# NerfPWM_V1_1.net
KiCad netlist of a schematic drawn in EAGLE
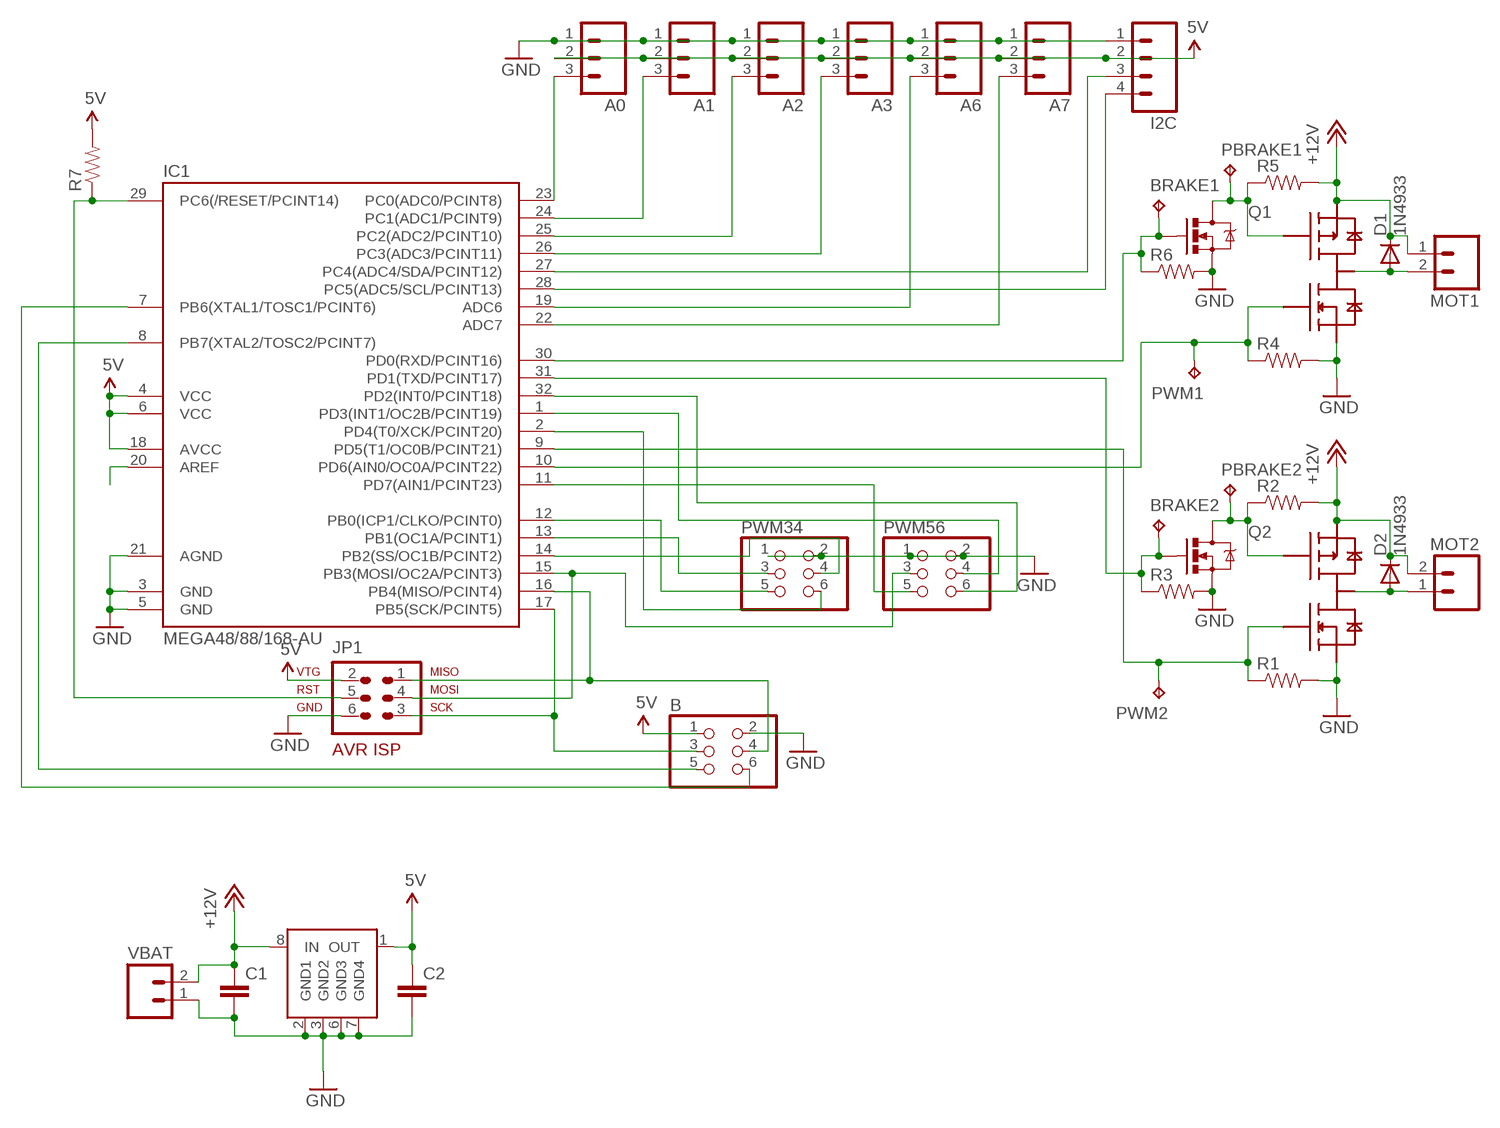
[diagram p0: schematic, sheet 1]

(export (version "E")
  (design (tool "Eeschema 10.0.6"))
  (components
    (comp (ref "A0")
      (value "M03PTH")
      (footprint "eagle-import:1X03")
      (libsource (lib "eagle-import") (part "M03PTH"))
    )
    (comp (ref "A1")
      (value "M03PTH")
      (footprint "eagle-import:1X03")
      (libsource (lib "eagle-import") (part "M03PTH"))
    )
    (comp (ref "A2")
      (value "M03PTH")
      (footprint "eagle-import:1X03")
      (libsource (lib "eagle-import") (part "M03PTH"))
    )
    (comp (ref "A3")
      (value "M03PTH")
      (footprint "eagle-import:1X03")
      (libsource (lib "eagle-import") (part "M03PTH"))
    )
    (comp (ref "A6")
      (value "M03PTH")
      (footprint "eagle-import:1X03")
      (libsource (lib "eagle-import") (part "M03PTH"))
    )
    (comp (ref "A7")
      (value "M03PTH")
      (footprint "eagle-import:1X03")
      (libsource (lib "eagle-import") (part "M03PTH"))
    )
    (comp (ref "B")
      (value "PINHD-2X3")
      (footprint "eagle-import:2X03")
      (libsource (lib "eagle-import") (part "PINHD-2X3"))
    )
    (comp (ref "BRAKE1")
      (value "TPTP10R")
      (footprint "eagle-import:TP10R")
      (libsource (lib "eagle-import") (part "TPTP10R"))
    )
    (comp (ref "BRAKE2")
      (value "TPTP10R")
      (footprint "eagle-import:TP10R")
      (libsource (lib "eagle-import") (part "TPTP10R"))
    )
    (comp (ref "C1")
      (value "CAP1206")
      (footprint "eagle-import:1206")
      (libsource (lib "eagle-import") (part "CAP1206"))
    )
    (comp (ref "C2")
      (value "CAP1206")
      (footprint "eagle-import:1206")
      (libsource (lib "eagle-import") (part "CAP1206"))
    )
    (comp (ref "D1")
      (value "1N4933")
      (footprint "eagle-import:DO41-10")
      (libsource (lib "eagle-import") (part "1N4933"))
    )
    (comp (ref "D2")
      (value "1N4933")
      (footprint "eagle-import:DO41-10")
      (libsource (lib "eagle-import") (part "1N4933"))
    )
    (comp (ref "I2C")
      (value "M04PTH")
      (footprint "eagle-import:1X04")
      (libsource (lib "eagle-import") (part "M04PTH"))
    )
    (comp (ref "IC1")
      (value "MEGA48/88/168-AU")
      (footprint "eagle-import:TQFP32-08")
      (libsource (lib "eagle-import") (part "MEGA48/88/168-AU"))
    )
    (comp (ref "JP1")
      (value "AVR-ISP-6")
      (footprint "eagle-import:AVR-ISP-6")
      (libsource (lib "eagle-import") (part "AVR-ISP-6"))
    )
    (comp (ref "MOT1")
      (value "M023.5MM_LOCK")
      (footprint "eagle-import:SCREWTERMINAL-3.5MM-2_LOCK")
      (libsource (lib "eagle-import") (part "M023.5MM_LOCK"))
    )
    (comp (ref "MOT2")
      (value "M023.5MM_LOCK")
      (footprint "eagle-import:SCREWTERMINAL-3.5MM-2_LOCK")
      (libsource (lib "eagle-import") (part "M023.5MM_LOCK"))
    )
    (comp (ref "PBRAKE1")
      (value "TPTP10R")
      (footprint "eagle-import:TP10R")
      (libsource (lib "eagle-import") (part "TPTP10R"))
    )
    (comp (ref "PBRAKE2")
      (value "TPTP10R")
      (footprint "eagle-import:TP10R")
      (libsource (lib "eagle-import") (part "TPTP10R"))
    )
    (comp (ref "PWM1")
      (value "TPTP10R")
      (footprint "eagle-import:TP10R")
      (libsource (lib "eagle-import") (part "TPTP10R"))
    )
    (comp (ref "PWM2")
      (value "TPTP10R")
      (footprint "eagle-import:TP10R")
      (libsource (lib "eagle-import") (part "TPTP10R"))
    )
    (comp (ref "PWM34")
      (value "PINHD-2X3")
      (footprint "eagle-import:2X03")
      (libsource (lib "eagle-import") (part "PINHD-2X3"))
    )
    (comp (ref "PWM56")
      (value "PINHD-2X3")
      (footprint "eagle-import:2X03")
      (libsource (lib "eagle-import") (part "PINHD-2X3"))
    )
    (comp (ref "Q1")
      (value "MOSFET-NCHANNELSMD")
      (footprint "eagle-import:SOT23-3")
      (libsource (lib "eagle-import") (part "MOSFET-NCHANNELSMD"))
    )
    (comp (ref "Q2")
      (value "MOSFET-NCHANNELSMD")
      (footprint "eagle-import:SOT23-3")
      (libsource (lib "eagle-import") (part "MOSFET-NCHANNELSMD"))
    )
    (comp (ref "R1")
      (value "RESISTOR")
      (footprint "eagle-import:0805")
      (libsource (lib "eagle-import") (part "RESISTOR"))
    )
    (comp (ref "R2")
      (value "RESISTOR")
      (footprint "eagle-import:0805")
      (libsource (lib "eagle-import") (part "RESISTOR"))
    )
    (comp (ref "R3")
      (value "RESISTOR")
      (footprint "eagle-import:0805")
      (libsource (lib "eagle-import") (part "RESISTOR"))
    )
    (comp (ref "R4")
      (value "RESISTOR")
      (footprint "eagle-import:0805")
      (libsource (lib "eagle-import") (part "RESISTOR"))
    )
    (comp (ref "R5")
      (value "RESISTOR")
      (footprint "eagle-import:0805")
      (libsource (lib "eagle-import") (part "RESISTOR"))
    )
    (comp (ref "R6")
      (value "RESISTOR")
      (footprint "eagle-import:0805")
      (libsource (lib "eagle-import") (part "RESISTOR"))
    )
    (comp (ref "R7")
      (value "RESISTOR")
      (footprint "eagle-import:0805")
      (libsource (lib "eagle-import") (part "RESISTOR"))
    )
    (comp (ref "U$3")
      (value "MC78L00AD")
      (footprint "eagle-import:SOIC8")
      (libsource (lib "eagle-import") (part "MC78L00AD"))
    )
    (comp (ref "U$4")
      (value "SI4501BDY")
      (footprint "eagle-import:SOIC8")
      (libsource (lib "eagle-import") (part "SI4501BDY"))
    )
    (comp (ref "U$5")
      (value "SI4501BDY")
      (footprint "eagle-import:SOIC8")
      (libsource (lib "eagle-import") (part "SI4501BDY"))
    )
    (comp (ref "VBAT")
      (value "M023.5MM_LOCK")
      (footprint "eagle-import:SCREWTERMINAL-3.5MM-2_LOCK")
      (libsource (lib "eagle-import") (part "M023.5MM_LOCK"))
    )
  )
  (nets
    (net (code "1") (name "+12V") (class "Default")
      (node (ref "C1") (pin "1") (pinfunction "1_1") (pintype "passive"))
      (node (ref "D1") (pin "C") (pinfunction "C_C") (pintype "passive"))
      (node (ref "D2") (pin "C") (pinfunction "C_C") (pintype "passive"))
      (node (ref "MOT1") (pin "1") (pinfunction "1_1") (pintype "passive"))
      (node (ref "MOT2") (pin "2") (pinfunction "2_2") (pintype "passive"))
      (node (ref "R2") (pin "2") (pinfunction "2_2") (pintype "passive"))
      (node (ref "R5") (pin "2") (pinfunction "2_2") (pintype "passive"))
      (node (ref "U$3") (pin "8") (pinfunction "IN_8") (pintype "power_in"))
      (node (ref "U$4") (pin "3") (pinfunction "S2_3") (pintype "power_in"))
      (node (ref "U$5") (pin "3") (pinfunction "S2_3") (pintype "power_in"))
      (node (ref "VBAT") (pin "2") (pinfunction "2_2") (pintype "passive"))
    )
    (net (code "2") (name "5V") (class "Default")
      (node (ref "A0") (pin "2") (pinfunction "2_2") (pintype "passive"))
      (node (ref "A1") (pin "2") (pinfunction "2_2") (pintype "passive"))
      (node (ref "A2") (pin "2") (pinfunction "2_2") (pintype "passive"))
      (node (ref "A3") (pin "2") (pinfunction "2_2") (pintype "passive"))
      (node (ref "A6") (pin "2") (pinfunction "2_2") (pintype "passive"))
      (node (ref "A7") (pin "2") (pinfunction "2_2") (pintype "passive"))
      (node (ref "B") (pin "1") (pinfunction "1_1") (pintype "passive"))
      (node (ref "C2") (pin "1") (pinfunction "1_1") (pintype "passive"))
      (node (ref "I2C") (pin "2") (pinfunction "2_2") (pintype "passive"))
      (node (ref "IC1") (pin "18") (pinfunction "AVCC_18") (pintype "passive"))
      (node (ref "IC1") (pin "4") (pinfunction "VCC_4") (pintype "power_in"))
      (node (ref "IC1") (pin "6") (pinfunction "VCC_6") (pintype "power_in"))
      (node (ref "JP1") (pin "2") (pinfunction "2_2") (pintype "passive"))
      (node (ref "R7") (pin "2") (pinfunction "2_2") (pintype "passive"))
      (node (ref "U$3") (pin "1") (pinfunction "OUT_1") (pintype "power_in"))
    )
    (net (code "3") (name "GND") (class "Default")
      (node (ref "A0") (pin "1") (pinfunction "1_1") (pintype "passive"))
      (node (ref "A1") (pin "1") (pinfunction "1_1") (pintype "passive"))
      (node (ref "A2") (pin "1") (pinfunction "1_1") (pintype "passive"))
      (node (ref "A3") (pin "1") (pinfunction "1_1") (pintype "passive"))
      (node (ref "A6") (pin "1") (pinfunction "1_1") (pintype "passive"))
      (node (ref "A7") (pin "1") (pinfunction "1_1") (pintype "passive"))
      (node (ref "B") (pin "2") (pinfunction "2_2") (pintype "passive"))
      (node (ref "C1") (pin "2") (pinfunction "2_2") (pintype "passive"))
      (node (ref "C2") (pin "2") (pinfunction "2_2") (pintype "passive"))
      (node (ref "I2C") (pin "1") (pinfunction "1_1") (pintype "passive"))
      (node (ref "IC1") (pin "21") (pinfunction "AGND_21") (pintype "power_in"))
      (node (ref "IC1") (pin "3") (pinfunction "GND_3") (pintype "power_in"))
      (node (ref "IC1") (pin "5") (pinfunction "GND_5") (pintype "power_in"))
      (node (ref "JP1") (pin "6") (pinfunction "6_6") (pintype "passive"))
      (node (ref "PWM34") (pin "1") (pinfunction "1_1") (pintype "passive"))
      (node (ref "PWM34") (pin "2") (pinfunction "2_2") (pintype "passive"))
      (node (ref "PWM56") (pin "1") (pinfunction "1_1") (pintype "passive"))
      (node (ref "PWM56") (pin "2") (pinfunction "2_2") (pintype "passive"))
      (node (ref "Q1") (pin "2") (pinfunction "S_2") (pintype "passive"))
      (node (ref "Q2") (pin "2") (pinfunction "S_2") (pintype "passive"))
      (node (ref "R1") (pin "2") (pinfunction "2_2") (pintype "passive"))
      (node (ref "R3") (pin "2") (pinfunction "2_2") (pintype "passive"))
      (node (ref "R4") (pin "2") (pinfunction "2_2") (pintype "passive"))
      (node (ref "R6") (pin "2") (pinfunction "2_2") (pintype "passive"))
      (node (ref "U$3") (pin "2") (pinfunction "GND1_2") (pintype "power_in"))
      (node (ref "U$3") (pin "3") (pinfunction "GND2_3") (pintype "power_in"))
      (node (ref "U$3") (pin "6") (pinfunction "GND3_6") (pintype "power_in"))
      (node (ref "U$3") (pin "7") (pinfunction "GND4_7") (pintype "power_in"))
      (node (ref "U$4") (pin "1") (pinfunction "S1_1") (pintype "power_in"))
      (node (ref "U$5") (pin "1") (pinfunction "S1_1") (pintype "power_in"))
      (node (ref "VBAT") (pin "1") (pinfunction "1_1") (pintype "passive"))
    )
    (net (code "4") (name "Net-(D1-PadA)") (class "Default")
      (node (ref "D1") (pin "A") (pinfunction "A_A") (pintype "passive"))
      (node (ref "MOT1") (pin "2") (pinfunction "2_2") (pintype "passive"))
      (node (ref "U$4") (pin "5") (pinfunction "D_5") (pintype "output"))
      (node (ref "U$4") (pin "6") (pinfunction "D_6") (pintype "output"))
      (node (ref "U$4") (pin "7") (pinfunction "D_7") (pintype "output"))
      (node (ref "U$4") (pin "8") (pinfunction "D_8") (pintype "output"))
    )
    (net (code "5") (name "Net-(D2-PadA)") (class "Default")
      (node (ref "D2") (pin "A") (pinfunction "A_A") (pintype "passive"))
      (node (ref "MOT2") (pin "1") (pinfunction "1_1") (pintype "passive"))
      (node (ref "U$5") (pin "5") (pinfunction "D_5") (pintype "output"))
      (node (ref "U$5") (pin "6") (pinfunction "D_6") (pintype "output"))
      (node (ref "U$5") (pin "7") (pinfunction "D_7") (pintype "output"))
      (node (ref "U$5") (pin "8") (pinfunction "D_8") (pintype "output"))
    )
    (net (code "6") (name "Net-(IC1-ADC6)") (class "Default")
      (node (ref "A6") (pin "3") (pinfunction "3_3") (pintype "passive"))
      (node (ref "IC1") (pin "19") (pinfunction "ADC6_19") (pintype "passive"))
    )
    (net (code "7") (name "Net-(IC1-ADC7)") (class "Default")
      (node (ref "A7") (pin "3") (pinfunction "3_3") (pintype "passive"))
      (node (ref "IC1") (pin "22") (pinfunction "ADC7_22") (pintype "passive"))
    )
    (net (code "8") (name "Net-(IC1-PB0(ICP1{slash}CLKO{slash}PCINT0))") (class "Default")
      (node (ref "IC1") (pin "12") (pinfunction "PB0(ICP1/CLKO/PCINT0)_12") (pintype "bidirectional"))
      (node (ref "PWM34") (pin "5") (pinfunction "5_5") (pintype "passive"))
    )
    (net (code "9") (name "Net-(IC1-PB1(OC1A{slash}PCINT1))") (class "Default")
      (node (ref "IC1") (pin "13") (pinfunction "PB1(OC1A/PCINT1)_13") (pintype "bidirectional"))
      (node (ref "PWM34") (pin "3") (pinfunction "3_3") (pintype "passive"))
    )
    (net (code "10") (name "Net-(IC1-PB2(SS{slash}OC1B{slash}PCINT2))") (class "Default")
      (node (ref "IC1") (pin "14") (pinfunction "PB2(SS/OC1B/PCINT2)_14") (pintype "bidirectional"))
      (node (ref "PWM34") (pin "4") (pinfunction "4_4") (pintype "passive"))
    )
    (net (code "11") (name "Net-(IC1-PB3(MOSI{slash}OC2A{slash}PCINT3))") (class "Default")
      (node (ref "IC1") (pin "15") (pinfunction "PB3(MOSI/OC2A/PCINT3)_15") (pintype "bidirectional"))
      (node (ref "JP1") (pin "4") (pinfunction "4_4") (pintype "passive"))
      (node (ref "PWM56") (pin "3") (pinfunction "3_3") (pintype "passive"))
    )
    (net (code "12") (name "Net-(IC1-PB4(MISO{slash}PCINT4))") (class "Default")
      (node (ref "B") (pin "4") (pinfunction "4_4") (pintype "passive"))
      (node (ref "IC1") (pin "16") (pinfunction "PB4(MISO/PCINT4)_16") (pintype "bidirectional"))
      (node (ref "JP1") (pin "1") (pinfunction "1_1") (pintype "passive"))
    )
    (net (code "13") (name "Net-(IC1-PB5(SCK{slash}PCINT5))") (class "Default")
      (node (ref "B") (pin "3") (pinfunction "3_3") (pintype "passive"))
      (node (ref "IC1") (pin "17") (pinfunction "PB5(SCK/PCINT5)_17") (pintype "bidirectional"))
      (node (ref "JP1") (pin "3") (pinfunction "3_3") (pintype "passive"))
    )
    (net (code "14") (name "Net-(IC1-PB6(XTAL1{slash}TOSC1{slash}PCINT6))") (class "Default")
      (node (ref "B") (pin "6") (pinfunction "6_6") (pintype "passive"))
      (node (ref "IC1") (pin "7") (pinfunction "PB6(XTAL1/TOSC1/PCINT6)_7") (pintype "bidirectional"))
    )
    (net (code "15") (name "Net-(IC1-PB7(XTAL2{slash}TOSC2{slash}PCINT7))") (class "Default")
      (node (ref "B") (pin "5") (pinfunction "5_5") (pintype "passive"))
      (node (ref "IC1") (pin "8") (pinfunction "PB7(XTAL2/TOSC2/PCINT7)_8") (pintype "bidirectional"))
    )
    (net (code "16") (name "Net-(IC1-PC0(ADC0{slash}PCINT8))") (class "Default")
      (node (ref "A0") (pin "3") (pinfunction "3_3") (pintype "passive"))
      (node (ref "IC1") (pin "23") (pinfunction "PC0(ADC0/PCINT8)_23") (pintype "bidirectional"))
    )
    (net (code "17") (name "Net-(IC1-PC1(ADC1{slash}PCINT9))") (class "Default")
      (node (ref "A1") (pin "3") (pinfunction "3_3") (pintype "passive"))
      (node (ref "IC1") (pin "24") (pinfunction "PC1(ADC1/PCINT9)_24") (pintype "bidirectional"))
    )
    (net (code "18") (name "Net-(IC1-PC2(ADC2{slash}PCINT10))") (class "Default")
      (node (ref "A2") (pin "3") (pinfunction "3_3") (pintype "passive"))
      (node (ref "IC1") (pin "25") (pinfunction "PC2(ADC2/PCINT10)_25") (pintype "bidirectional"))
    )
    (net (code "19") (name "Net-(IC1-PC3(ADC3{slash}PCINT11))") (class "Default")
      (node (ref "A3") (pin "3") (pinfunction "3_3") (pintype "passive"))
      (node (ref "IC1") (pin "26") (pinfunction "PC3(ADC3/PCINT11)_26") (pintype "bidirectional"))
    )
    (net (code "20") (name "Net-(IC1-PC4(ADC4{slash}SDA{slash}PCINT12))") (class "Default")
      (node (ref "I2C") (pin "3") (pinfunction "3_3") (pintype "passive"))
      (node (ref "IC1") (pin "27") (pinfunction "PC4(ADC4/SDA/PCINT12)_27") (pintype "bidirectional"))
    )
    (net (code "21") (name "Net-(IC1-PC5(ADC5{slash}SCL{slash}PCINT13))") (class "Default")
      (node (ref "I2C") (pin "4") (pinfunction "4_4") (pintype "passive"))
      (node (ref "IC1") (pin "28") (pinfunction "PC5(ADC5/SCL/PCINT13)_28") (pintype "bidirectional"))
    )
    (net (code "22") (name "Net-(IC1-PC6({slash}RESET{slash}PCINT14))") (class "Default")
      (node (ref "IC1") (pin "29") (pinfunction "PC6(/RESET/PCINT14)_29") (pintype "bidirectional"))
      (node (ref "JP1") (pin "5") (pinfunction "5_5") (pintype "passive"))
      (node (ref "R7") (pin "1") (pinfunction "1_1") (pintype "passive"))
    )
    (net (code "23") (name "Net-(IC1-PD0(RXD{slash}PCINT16))") (class "Default")
      (node (ref "BRAKE1") (pin "TP") (pinfunction "TP_TP") (pintype "input"))
      (node (ref "IC1") (pin "30") (pinfunction "PD0(RXD/PCINT16)_30") (pintype "bidirectional"))
      (node (ref "Q1") (pin "1") (pinfunction "G_1") (pintype "passive"))
      (node (ref "R6") (pin "1") (pinfunction "1_1") (pintype "passive"))
    )
    (net (code "24") (name "Net-(IC1-PD1(TXD{slash}PCINT17))") (class "Default")
      (node (ref "BRAKE2") (pin "TP") (pinfunction "TP_TP") (pintype "input"))
      (node (ref "IC1") (pin "31") (pinfunction "PD1(TXD/PCINT17)_31") (pintype "bidirectional"))
      (node (ref "Q2") (pin "1") (pinfunction "G_1") (pintype "passive"))
      (node (ref "R3") (pin "1") (pinfunction "1_1") (pintype "passive"))
    )
    (net (code "25") (name "Net-(IC1-PD2(INT0{slash}PCINT18))") (class "Default")
      (node (ref "IC1") (pin "32") (pinfunction "PD2(INT0/PCINT18)_32") (pintype "bidirectional"))
      (node (ref "PWM56") (pin "6") (pinfunction "6_6") (pintype "passive"))
    )
    (net (code "26") (name "Net-(IC1-PD3(INT1{slash}OC2B{slash}PCINT19))") (class "Default")
      (node (ref "IC1") (pin "1") (pinfunction "PD3(INT1/OC2B/PCINT19)_1") (pintype "bidirectional"))
      (node (ref "PWM56") (pin "4") (pinfunction "4_4") (pintype "passive"))
    )
    (net (code "27") (name "Net-(IC1-PD4(T0{slash}XCK{slash}PCINT20))") (class "Default")
      (node (ref "IC1") (pin "2") (pinfunction "PD4(T0/XCK/PCINT20)_2") (pintype "bidirectional"))
      (node (ref "PWM34") (pin "6") (pinfunction "6_6") (pintype "passive"))
    )
    (net (code "28") (name "Net-(IC1-PD5(T1{slash}OC0B{slash}PCINT21))") (class "Default")
      (node (ref "IC1") (pin "9") (pinfunction "PD5(T1/OC0B/PCINT21)_9") (pintype "bidirectional"))
      (node (ref "PWM2") (pin "TP") (pinfunction "TP_TP") (pintype "input"))
      (node (ref "R1") (pin "1") (pinfunction "1_1") (pintype "passive"))
      (node (ref "U$5") (pin "2") (pinfunction "G1_2") (pintype "input"))
    )
    (net (code "29") (name "Net-(IC1-PD6(AIN0{slash}OC0A{slash}PCINT22))") (class "Default")
      (node (ref "IC1") (pin "10") (pinfunction "PD6(AIN0/OC0A/PCINT22)_10") (pintype "bidirectional"))
      (node (ref "PWM1") (pin "TP") (pinfunction "TP_TP") (pintype "input"))
      (node (ref "R4") (pin "1") (pinfunction "1_1") (pintype "passive"))
      (node (ref "U$4") (pin "2") (pinfunction "G1_2") (pintype "input"))
    )
    (net (code "30") (name "Net-(IC1-PD7(AIN1{slash}PCINT23))") (class "Default")
      (node (ref "IC1") (pin "11") (pinfunction "PD7(AIN1/PCINT23)_11") (pintype "bidirectional"))
      (node (ref "PWM56") (pin "5") (pinfunction "5_5") (pintype "passive"))
    )
    (net (code "31") (name "Net-(Q1-D)") (class "Default")
      (node (ref "PBRAKE1") (pin "TP") (pinfunction "TP_TP") (pintype "input"))
      (node (ref "Q1") (pin "3") (pinfunction "D_3") (pintype "passive"))
      (node (ref "R5") (pin "1") (pinfunction "1_1") (pintype "passive"))
      (node (ref "U$4") (pin "4") (pinfunction "G2_4") (pintype "input"))
    )
    (net (code "32") (name "Net-(Q2-D)") (class "Default")
      (node (ref "PBRAKE2") (pin "TP") (pinfunction "TP_TP") (pintype "input"))
      (node (ref "Q2") (pin "3") (pinfunction "D_3") (pintype "passive"))
      (node (ref "R2") (pin "1") (pinfunction "1_1") (pintype "passive"))
      (node (ref "U$5") (pin "4") (pinfunction "G2_4") (pintype "input"))
    )
    (net (code "33") (name "unconnected-(IC1-AREF-Pad20)") (class "Default")
      (node (ref "IC1") (pin "20") (pinfunction "AREF_20") (pintype "passive"))
    )
  )
)
